# espism-v2.net
KiCad netlist of a schematic drawn in EAGLE
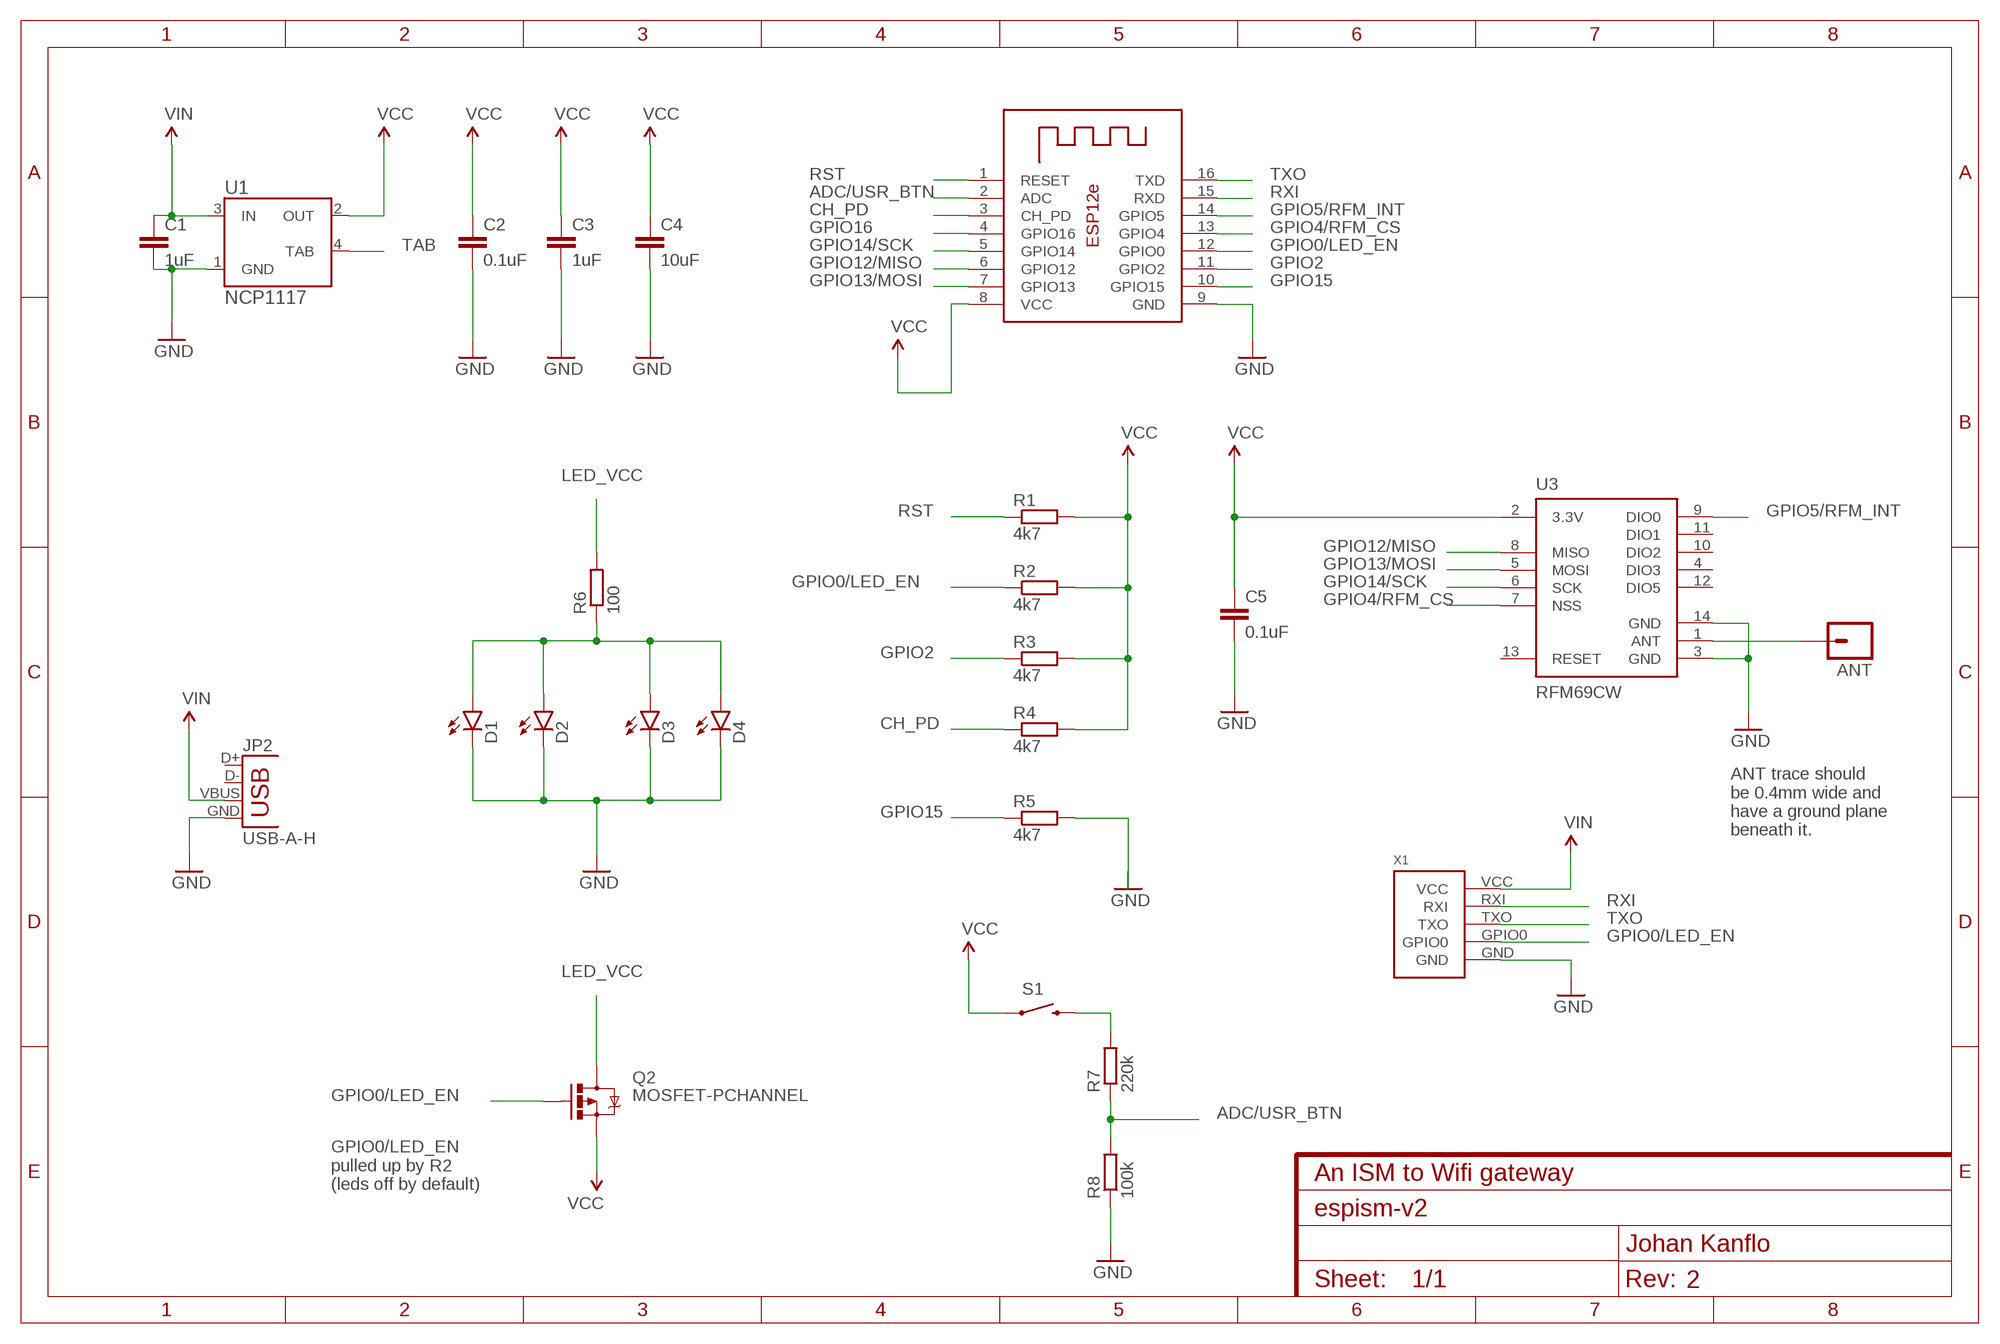
[diagram p0: schematic, sheet 1]

(export (version "E")
  (design (tool "Eeschema 10.0.6"))
  (components
    (comp (ref "ANT")
      (value "M01PTH")
      (footprint "eagle-import:1X01")
      (libsource (lib "eagle-import") (part "M01PTH"))
    )
    (comp (ref "C1")
      (value "1uF")
      (footprint "eagle-import:0603-CAP")
      (libsource (lib "eagle-import") (part "CAP0603-CAP"))
    )
    (comp (ref "C2")
      (value "0.1uF")
      (footprint "eagle-import:0603-CAP")
      (libsource (lib "eagle-import") (part "CAP0603-CAP"))
    )
    (comp (ref "C3")
      (value "1uF")
      (footprint "eagle-import:0603-CAP")
      (libsource (lib "eagle-import") (part "CAP0603-CAP"))
    )
    (comp (ref "C4")
      (value "10uF")
      (footprint "eagle-import:0603-CAP")
      (libsource (lib "eagle-import") (part "CAP0603-CAP"))
    )
    (comp (ref "C5")
      (value "0.1uF")
      (footprint "eagle-import:0603-CAP")
      (libsource (lib "eagle-import") (part "CAP0603-CAP"))
    )
    (comp (ref "D1")
      (value "LED0603")
      (footprint "eagle-import:LED-0603")
      (libsource (lib "eagle-import") (part "LED0603"))
    )
    (comp (ref "D2")
      (value "LED0603")
      (footprint "eagle-import:LED-0603")
      (libsource (lib "eagle-import") (part "LED0603"))
    )
    (comp (ref "D3")
      (value "LED0603")
      (footprint "eagle-import:LED-0603")
      (libsource (lib "eagle-import") (part "LED0603"))
    )
    (comp (ref "D4")
      (value "LED0603")
      (footprint "eagle-import:LED-0603")
      (libsource (lib "eagle-import") (part "LED0603"))
    )
    (comp (ref "JP2")
      (value "USB-A-H")
      (footprint "eagle-import:USB-A-H")
      (libsource (lib "eagle-import") (part "USB-A-H"))
    )
    (comp (ref "Q2")
      (value "MOSFET-PCHANNEL")
      (footprint "eagle-import:SOT23-3")
      (libsource (lib "eagle-import") (part "MOSFET-PCHANNEL"))
    )
    (comp (ref "R1")
      (value "4k7")
      (footprint "eagle-import:R0603")
      (libsource (lib "eagle-import") (part "R-EU_R0603"))
    )
    (comp (ref "R2")
      (value "4k7")
      (footprint "eagle-import:R0603")
      (libsource (lib "eagle-import") (part "R-EU_R0603"))
    )
    (comp (ref "R3")
      (value "4k7")
      (footprint "eagle-import:R0603")
      (libsource (lib "eagle-import") (part "R-EU_R0603"))
    )
    (comp (ref "R4")
      (value "4k7")
      (footprint "eagle-import:R0603")
      (libsource (lib "eagle-import") (part "R-EU_R0603"))
    )
    (comp (ref "R5")
      (value "4k7")
      (footprint "eagle-import:R0603")
      (libsource (lib "eagle-import") (part "R-EU_R0603"))
    )
    (comp (ref "R6")
      (value "100")
      (footprint "eagle-import:R0603")
      (libsource (lib "eagle-import") (part "R-EU_R0603"))
    )
    (comp (ref "R7")
      (value "220k")
      (footprint "eagle-import:R0603")
      (libsource (lib "eagle-import") (part "R-EU_R0603"))
    )
    (comp (ref "R8")
      (value "100k")
      (footprint "eagle-import:R0603")
      (libsource (lib "eagle-import") (part "R-EU_R0603"))
    )
    (comp (ref "S1")
      (value "SWITCH-MOMENTARY-2SMD-1101NE")
      (footprint "eagle-import:TACTILE-SWITCH-1101NE")
      (libsource (lib "eagle-import") (part "SWITCH-MOMENTARY-2SMD-1101NE"))
    )
    (comp (ref "U1")
      (value "NCP1117")
      (footprint "eagle-import:SOT223")
      (libsource (lib "eagle-import") (part "NCP1117"))
    )
    (comp (ref "U2")
      (value "ESP-12E")
      (footprint "eagle-import:ESP-12E")
      (libsource (lib "eagle-import") (part "ESP-12E"))
    )
    (comp (ref "U3")
      (value "RFM69CW")
      (footprint "eagle-import:RFM69CW-XXXS2")
      (libsource (lib "eagle-import") (part "RFM69CW"))
    )
    (comp (ref "X1")
      (value "ESPROGESPROG-DEVICE")
      (footprint "eagle-import:ESPROG")
      (libsource (lib "eagle-import") (part "ESPROGESPROG-DEVICE"))
    )
  )
  (nets
    (net (code "1") (name "/ADC{slash}USR_BTN") (class "Default")
      (node (ref "R7") (pin "1") (pinfunction "1_1") (pintype "passive"))
      (node (ref "R8") (pin "2") (pinfunction "2_2") (pintype "passive"))
      (node (ref "U2") (pin "2") (pinfunction "ADC_2") (pintype "passive"))
    )
    (net (code "2") (name "/CH_PD") (class "Default")
      (node (ref "R4") (pin "1") (pinfunction "1_1") (pintype "passive"))
      (node (ref "U2") (pin "3") (pinfunction "CH_PD_3") (pintype "input"))
    )
    (net (code "3") (name "/GPIO0{slash}LED_EN") (class "Default")
      (node (ref "Q2") (pin "1") (pinfunction "G_1") (pintype "passive"))
      (node (ref "R2") (pin "1") (pinfunction "1_1") (pintype "passive"))
      (node (ref "U2") (pin "12") (pinfunction "GPIO0_12") (pintype "bidirectional"))
      (node (ref "X1") (pin "GPIO0") (pinfunction "GPIO0_GPIO0") (pintype "bidirectional"))
    )
    (net (code "4") (name "/GPIO2") (class "Default")
      (node (ref "R3") (pin "1") (pinfunction "1_1") (pintype "passive"))
      (node (ref "U2") (pin "11") (pinfunction "GPIO2_11") (pintype "bidirectional"))
    )
    (net (code "5") (name "/GPIO4{slash}RFM_CS") (class "Default")
      (node (ref "U2") (pin "13") (pinfunction "GPIO4_13") (pintype "bidirectional"))
      (node (ref "U3") (pin "7") (pinfunction "NSS_7") (pintype "input"))
    )
    (net (code "6") (name "/GPIO5{slash}RFM_INT") (class "Default")
      (node (ref "U2") (pin "14") (pinfunction "GPIO5_14") (pintype "bidirectional"))
      (node (ref "U3") (pin "9") (pinfunction "DIO0_9") (pintype "bidirectional"))
    )
    (net (code "7") (name "/GPIO12{slash}MISO") (class "Default")
      (node (ref "U2") (pin "6") (pinfunction "GPIO12_6") (pintype "bidirectional"))
      (node (ref "U3") (pin "8") (pinfunction "MISO_8") (pintype "bidirectional"))
    )
    (net (code "8") (name "/GPIO13{slash}MOSI") (class "Default")
      (node (ref "U2") (pin "7") (pinfunction "GPIO13_7") (pintype "bidirectional"))
      (node (ref "U3") (pin "5") (pinfunction "MOSI_5") (pintype "input"))
    )
    (net (code "9") (name "/GPIO14{slash}SCK") (class "Default")
      (node (ref "U2") (pin "5") (pinfunction "GPIO14_5") (pintype "bidirectional"))
      (node (ref "U3") (pin "6") (pinfunction "SCK_6") (pintype "input"))
    )
    (net (code "10") (name "/GPIO15") (class "Default")
      (node (ref "R5") (pin "1") (pinfunction "1_1") (pintype "passive"))
      (node (ref "U2") (pin "10") (pinfunction "GPIO15_10") (pintype "bidirectional"))
    )
    (net (code "11") (name "/GPIO16") (class "Default")
      (node (ref "U2") (pin "4") (pinfunction "GPIO16_4") (pintype "bidirectional"))
    )
    (net (code "12") (name "/LED_VCC") (class "Default")
      (node (ref "Q2") (pin "3") (pinfunction "D_3") (pintype "passive"))
      (node (ref "R6") (pin "2") (pinfunction "2_2") (pintype "passive"))
    )
    (net (code "13") (name "/RST") (class "Default")
      (node (ref "R1") (pin "1") (pinfunction "1_1") (pintype "passive"))
      (node (ref "U2") (pin "1") (pinfunction "RESET_1") (pintype "input"))
    )
    (net (code "14") (name "/RXI") (class "Default")
      (node (ref "U2") (pin "15") (pinfunction "RXD_15") (pintype "input"))
      (node (ref "X1") (pin "RXI") (pinfunction "RXI_RXI") (pintype "bidirectional"))
    )
    (net (code "15") (name "/TAB") (class "Default")
      (node (ref "U1") (pin "4") (pinfunction "TAB_4") (pintype "bidirectional"))
    )
    (net (code "16") (name "/TXO") (class "Default")
      (node (ref "U2") (pin "16") (pinfunction "TXD_16") (pintype "output"))
      (node (ref "X1") (pin "TXO") (pinfunction "TXO_TXO") (pintype "bidirectional"))
    )
    (net (code "17") (name "GND") (class "Default")
      (node (ref "C1") (pin "2") (pinfunction "2_2") (pintype "passive"))
      (node (ref "C2") (pin "2") (pinfunction "2_2") (pintype "passive"))
      (node (ref "C3") (pin "2") (pinfunction "2_2") (pintype "passive"))
      (node (ref "C4") (pin "2") (pinfunction "2_2") (pintype "passive"))
      (node (ref "C5") (pin "2") (pinfunction "2_2") (pintype "passive"))
      (node (ref "D1") (pin "C") (pinfunction "C_C") (pintype "passive"))
      (node (ref "D2") (pin "C") (pinfunction "C_C") (pintype "passive"))
      (node (ref "D3") (pin "C") (pinfunction "C_C") (pintype "passive"))
      (node (ref "D4") (pin "C") (pinfunction "C_C") (pintype "passive"))
      (node (ref "JP2") (pin "GND") (pinfunction "GND_GND") (pintype "bidirectional"))
      (node (ref "R5") (pin "2") (pinfunction "2_2") (pintype "passive"))
      (node (ref "R8") (pin "1") (pinfunction "1_1") (pintype "passive"))
      (node (ref "U1") (pin "1") (pinfunction "GND_1") (pintype "bidirectional"))
      (node (ref "U2") (pin "9") (pinfunction "GND_9") (pintype "power_in"))
      (node (ref "U3") (pin "14") (pinfunction "GND_14") (pintype "power_in"))
      (node (ref "U3") (pin "3") (pinfunction "GND_3") (pintype "power_in"))
      (node (ref "X1") (pin "GND") (pinfunction "GND_GND") (pintype "bidirectional"))
    )
    (net (code "18") (name "Net-(D1-PadA)") (class "Default")
      (node (ref "D1") (pin "A") (pinfunction "A_A") (pintype "passive"))
      (node (ref "D2") (pin "A") (pinfunction "A_A") (pintype "passive"))
      (node (ref "D3") (pin "A") (pinfunction "A_A") (pintype "passive"))
      (node (ref "D4") (pin "A") (pinfunction "A_A") (pintype "passive"))
      (node (ref "R6") (pin "1") (pinfunction "1_1") (pintype "passive"))
    )
    (net (code "19") (name "Net-(R7-Pad2)") (class "Default")
      (node (ref "R7") (pin "2") (pinfunction "2_2") (pintype "passive"))
      (node (ref "S1") (pin "2") (pinfunction "2_2") (pintype "passive"))
    )
    (net (code "20") (name "Net-(U3-ANT)") (class "Default")
      (node (ref "ANT") (pin "1") (pinfunction "1_1") (pintype "passive"))
      (node (ref "U3") (pin "1") (pinfunction "ANT_1") (pintype "passive"))
    )
    (net (code "21") (name "VCC") (class "Default")
      (node (ref "C2") (pin "1") (pinfunction "1_1") (pintype "passive"))
      (node (ref "C3") (pin "1") (pinfunction "1_1") (pintype "passive"))
      (node (ref "C4") (pin "1") (pinfunction "1_1") (pintype "passive"))
      (node (ref "C5") (pin "1") (pinfunction "1_1") (pintype "passive"))
      (node (ref "Q2") (pin "2") (pinfunction "S_2") (pintype "passive"))
      (node (ref "R1") (pin "2") (pinfunction "2_2") (pintype "passive"))
      (node (ref "R2") (pin "2") (pinfunction "2_2") (pintype "passive"))
      (node (ref "R3") (pin "2") (pinfunction "2_2") (pintype "passive"))
      (node (ref "R4") (pin "2") (pinfunction "2_2") (pintype "passive"))
      (node (ref "S1") (pin "1") (pinfunction "1_1") (pintype "passive"))
      (node (ref "U1") (pin "2") (pinfunction "OUT_2") (pintype "bidirectional"))
      (node (ref "U2") (pin "8") (pinfunction "VCC_8") (pintype "power_in"))
      (node (ref "U3") (pin "2") (pinfunction "3.3V_2") (pintype "power_in"))
    )
    (net (code "22") (name "VIN") (class "Default")
      (node (ref "C1") (pin "1") (pinfunction "1_1") (pintype "passive"))
      (node (ref "JP2") (pin "VBUS") (pinfunction "VBUS_VBUS") (pintype "bidirectional"))
      (node (ref "U1") (pin "3") (pinfunction "IN_3") (pintype "bidirectional"))
      (node (ref "X1") (pin "VCC") (pinfunction "VCC_VCC") (pintype "bidirectional"))
    )
    (net (code "23") (name "unconnected-(JP2-PadD+)") (class "Default")
      (node (ref "JP2") (pin "D+") (pinfunction "D+_D+") (pintype "bidirectional"))
    )
    (net (code "24") (name "unconnected-(JP2-PadD-)") (class "Default")
      (node (ref "JP2") (pin "D-") (pinfunction "D-_D-") (pintype "bidirectional"))
    )
    (net (code "25") (name "unconnected-(U3-DIO1-Pad11)") (class "Default")
      (node (ref "U3") (pin "11") (pinfunction "DIO1_11") (pintype "bidirectional"))
    )
    (net (code "26") (name "unconnected-(U3-DIO2-Pad10)") (class "Default")
      (node (ref "U3") (pin "10") (pinfunction "DIO2_10") (pintype "bidirectional"))
    )
    (net (code "27") (name "unconnected-(U3-DIO3-Pad4)") (class "Default")
      (node (ref "U3") (pin "4") (pinfunction "DIO3_4") (pintype "bidirectional"))
    )
    (net (code "28") (name "unconnected-(U3-DIO5-Pad12)") (class "Default")
      (node (ref "U3") (pin "12") (pinfunction "DIO5_12") (pintype "bidirectional"))
    )
    (net (code "29") (name "unconnected-(U3-RESET-Pad13)") (class "Default")
      (node (ref "U3") (pin "13") (pinfunction "RESET_13") (pintype "input"))
    )
  )
)
